# RFID.net
KiCad netlist of a schematic drawn in EAGLE
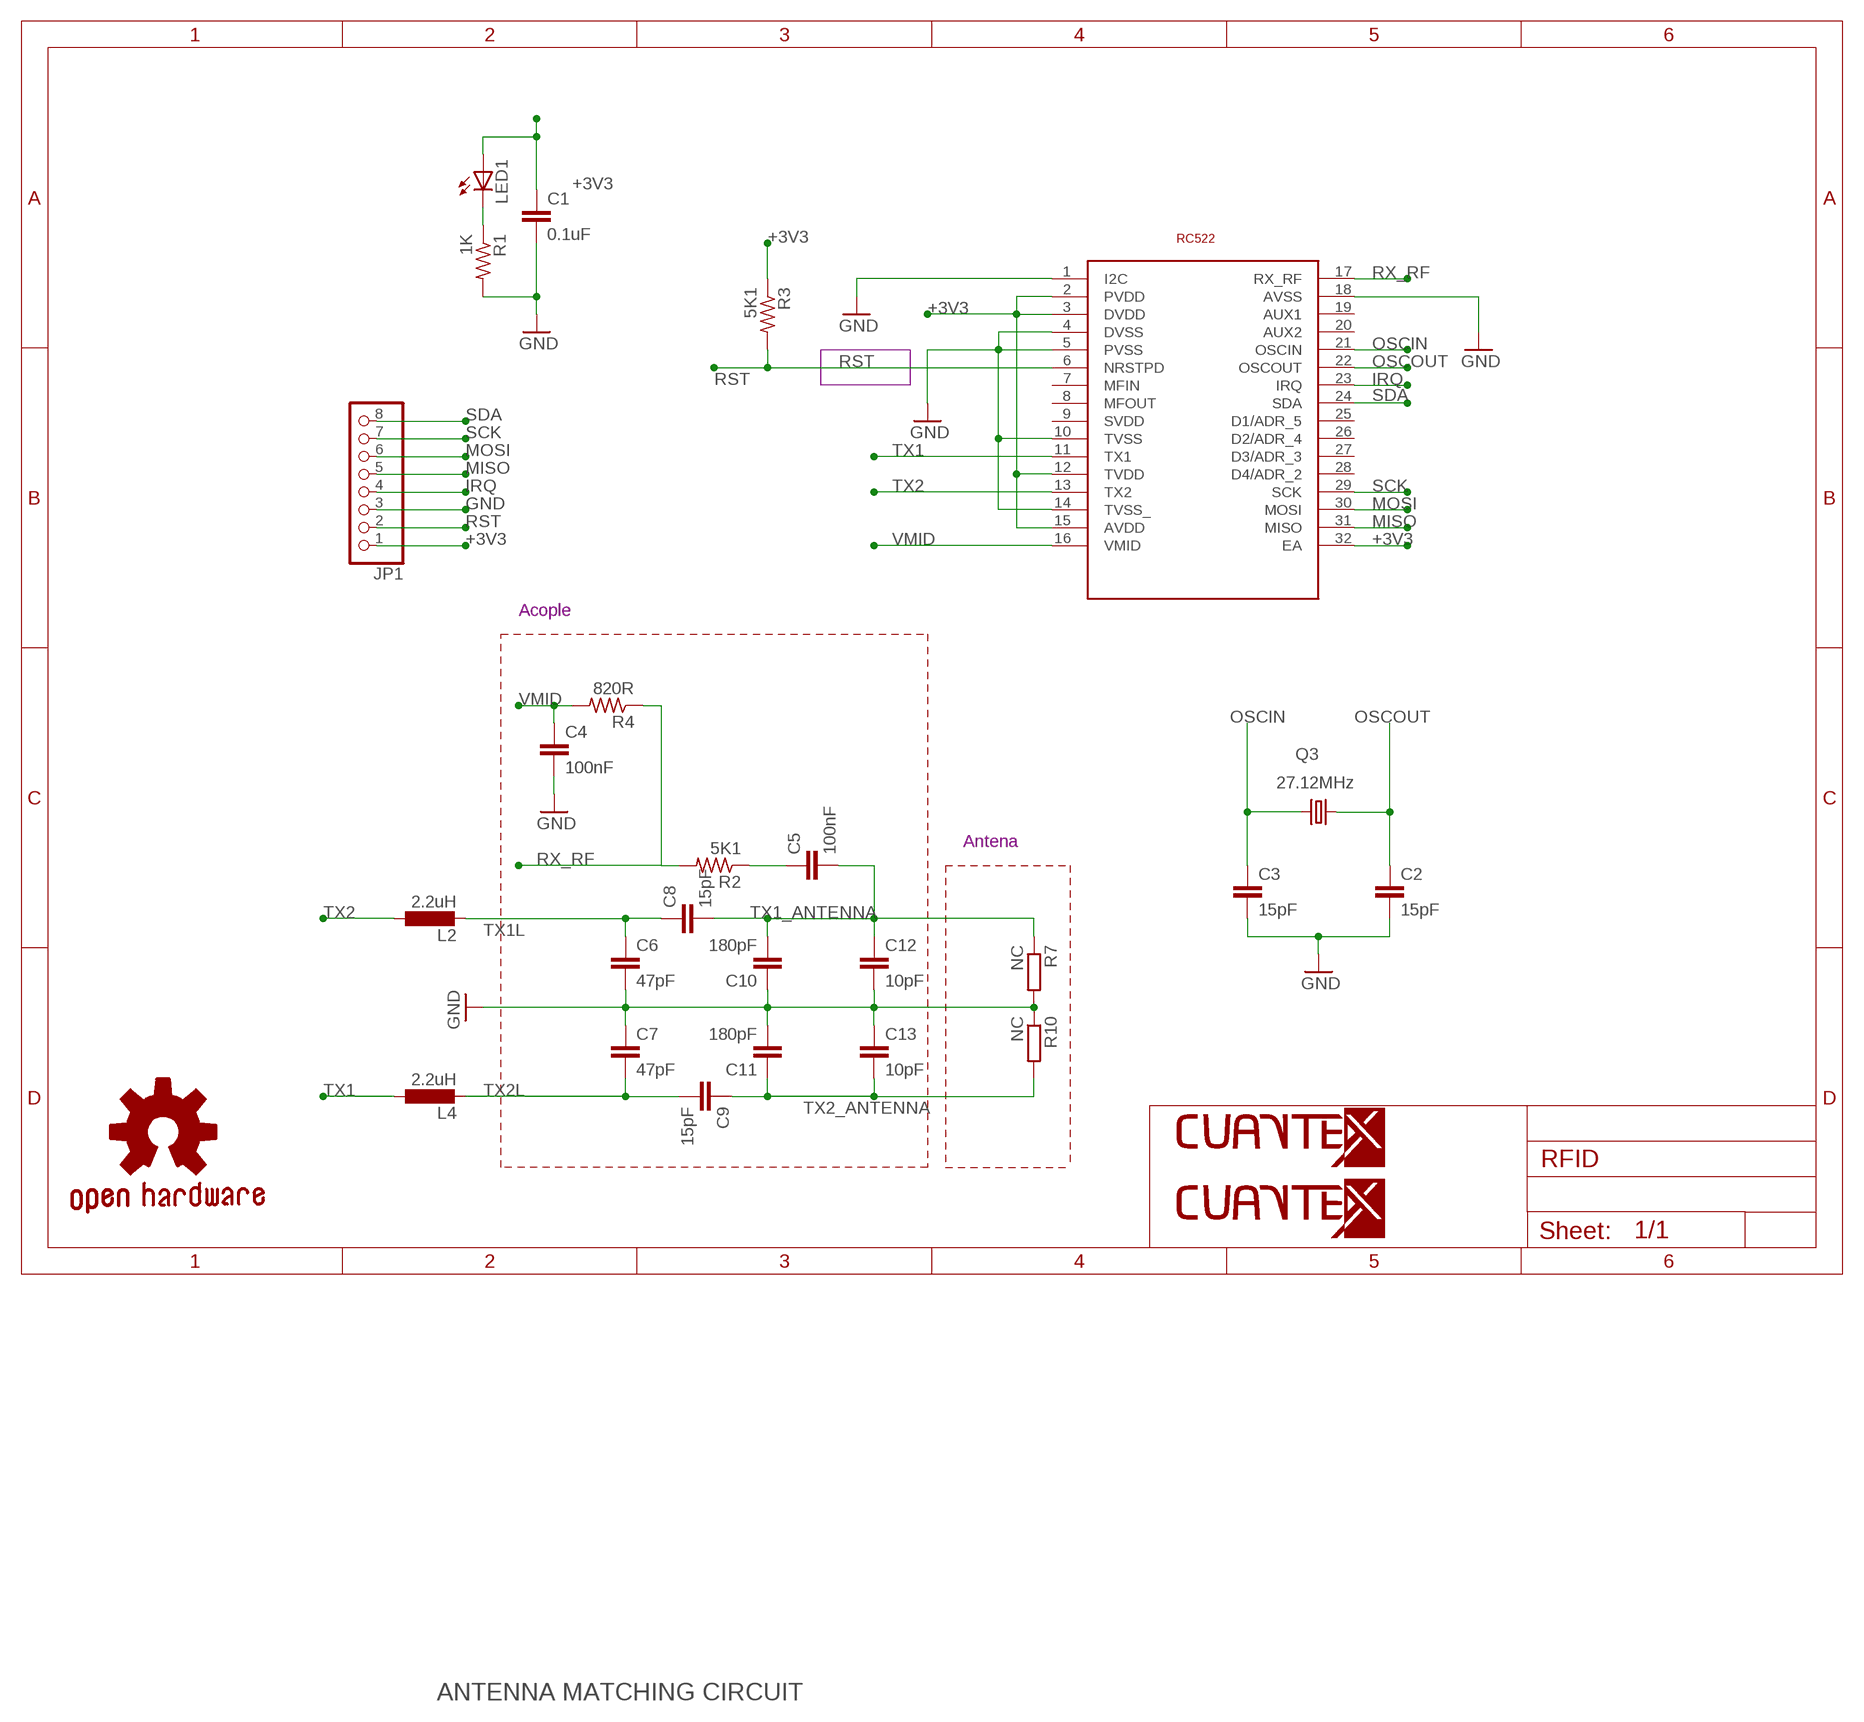
[diagram p0: schematic, sheet 1]

(export (version "E")
  (design (tool "Eeschema 10.0.6"))
  (components
    (comp (ref "C1")
      (value "0.1uF")
      (footprint "eagle-import:C0603K")
      (libsource (lib "eagle-import") (part "resistor_C-EUC0603K"))
    )
    (comp (ref "C2")
      (value "15pF")
      (footprint "eagle-import:C0603K")
      (libsource (lib "eagle-import") (part "C-EUC0603K"))
    )
    (comp (ref "C3")
      (value "15pF")
      (footprint "eagle-import:C0603K")
      (libsource (lib "eagle-import") (part "C-EUC0603K"))
    )
    (comp (ref "C4")
      (value "100nF")
      (footprint "eagle-import:C0603K")
      (libsource (lib "eagle-import") (part "C-EUC0603K"))
    )
    (comp (ref "C5")
      (value "100nF")
      (footprint "eagle-import:C0603K")
      (libsource (lib "eagle-import") (part "C-EUC0603K"))
    )
    (comp (ref "C6")
      (value "47pF")
      (footprint "eagle-import:C0603K")
      (libsource (lib "eagle-import") (part "C-EUC0603K"))
    )
    (comp (ref "C7")
      (value "47pF")
      (footprint "eagle-import:C0603K")
      (libsource (lib "eagle-import") (part "C-EUC0603K"))
    )
    (comp (ref "C8")
      (value "15pF")
      (footprint "eagle-import:C0603K")
      (libsource (lib "eagle-import") (part "C-EUC0603K"))
    )
    (comp (ref "C9")
      (value "15pF")
      (footprint "eagle-import:C0603K")
      (libsource (lib "eagle-import") (part "C-EUC0603K"))
    )
    (comp (ref "C10")
      (value "180pF")
      (footprint "eagle-import:C0603K")
      (libsource (lib "eagle-import") (part "C-EUC0603K"))
    )
    (comp (ref "C11")
      (value "180pF")
      (footprint "eagle-import:C0603K")
      (libsource (lib "eagle-import") (part "C-EUC0603K"))
    )
    (comp (ref "C12")
      (value "10pF")
      (footprint "eagle-import:C0603K")
      (libsource (lib "eagle-import") (part "C-EUC0603K"))
    )
    (comp (ref "C13")
      (value "10pF")
      (footprint "eagle-import:C0603K")
      (libsource (lib "eagle-import") (part "C-EUC0603K"))
    )
    (comp (ref "GOLD_ORB_SM1")
      (value "OSHWLOGO_GOLD_ORB_SM")
      (footprint "eagle-import:OSHW2")
      (libsource (lib "eagle-import") (part "OSHWLOGO_GOLD_ORB_SM"))
    )
    (comp (ref "JP1")
      (value "PINHD-1X8")
      (footprint "eagle-import:1X08")
      (libsource (lib "eagle-import") (part "PINHD-1X8"))
    )
    (comp (ref "L2")
      (value "2.2uH")
      (footprint "eagle-import:L2012C")
      (libsource (lib "eagle-import") (part "L-EUL2012C"))
    )
    (comp (ref "L4")
      (value "2.2uH")
      (footprint "eagle-import:L2012C")
      (libsource (lib "eagle-import") (part "L-EUL2012C"))
    )
    (comp (ref "LED1")
      (value "LED_E")
      (footprint "eagle-import:LED_1206")
      (libsource (lib "eagle-import") (part "LED_E"))
    )
    (comp (ref "Q3")
      (value "27.12MHz")
      (footprint "eagle-import:HC49UP")
      (libsource (lib "eagle-import") (part "CRYSTALHC49UP"))
    )
    (comp (ref "R1")
      (value "1K")
      (footprint "eagle-import:R0603")
      (libsource (lib "eagle-import") (part "R-US_R0603"))
    )
    (comp (ref "R2")
      (value "5K1")
      (footprint "eagle-import:R0603")
      (libsource (lib "eagle-import") (part "R-US_R0603"))
    )
    (comp (ref "R3")
      (value "5K1")
      (footprint "eagle-import:R0603")
      (libsource (lib "eagle-import") (part "R-US_R0603"))
    )
    (comp (ref "R4")
      (value "820R")
      (footprint "eagle-import:R0603")
      (libsource (lib "eagle-import") (part "R-US_R0603"))
    )
    (comp (ref "R7")
      (value "NC")
      (footprint "eagle-import:R0201")
      (libsource (lib "eagle-import") (part "R-EU_R0201"))
    )
    (comp (ref "R10")
      (value "NC")
      (footprint "eagle-import:R0201")
      (libsource (lib "eagle-import") (part "R-EU_R0201"))
    )
    (comp (ref "U$1")
      (value "LOGO-BOT-50MM")
      (footprint "eagle-import:B-50")
      (libsource (lib "eagle-import") (part "LOGO-BOT-50MM"))
    )
    (comp (ref "U$2")
      (value "LOGO-TOP-20MM")
      (footprint "eagle-import:C-0")
      (libsource (lib "eagle-import") (part "LOGO-TOP-20MM"))
    )
    (comp (ref "U1")
      (value "RC522")
      (footprint "eagle-import:HVQFN32")
      (libsource (lib "eagle-import") (part "RC522"))
    )
  )
  (nets
    (net (code "1") (name "/+3V3") (class "Default")
      (node (ref "C1") (pin "1") (pinfunction "1_1") (pintype "passive"))
      (node (ref "JP1") (pin "1") (pinfunction "1_1") (pintype "passive"))
      (node (ref "LED1") (pin "A") (pinfunction "A_A") (pintype "passive"))
      (node (ref "R3") (pin "1") (pinfunction "1_1") (pintype "passive"))
      (node (ref "U1") (pin "12") (pinfunction "TVDD_12") (pintype "bidirectional"))
      (node (ref "U1") (pin "15") (pinfunction "AVDD_15") (pintype "bidirectional"))
      (node (ref "U1") (pin "2") (pinfunction "PVDD_2") (pintype "bidirectional"))
      (node (ref "U1") (pin "3") (pinfunction "DVDD_3") (pintype "bidirectional"))
      (node (ref "U1") (pin "32") (pinfunction "EA_32") (pintype "bidirectional"))
    )
    (net (code "2") (name "/IRQ") (class "Default")
      (node (ref "JP1") (pin "4") (pinfunction "4_4") (pintype "passive"))
      (node (ref "U1") (pin "23") (pinfunction "IRQ_23") (pintype "bidirectional"))
    )
    (net (code "3") (name "/MISO") (class "Default")
      (node (ref "JP1") (pin "5") (pinfunction "5_5") (pintype "passive"))
      (node (ref "U1") (pin "31") (pinfunction "MISO_31") (pintype "bidirectional"))
    )
    (net (code "4") (name "/MOSI") (class "Default")
      (node (ref "JP1") (pin "6") (pinfunction "6_6") (pintype "passive"))
      (node (ref "U1") (pin "30") (pinfunction "MOSI_30") (pintype "bidirectional"))
    )
    (net (code "5") (name "/OSCIN") (class "Default")
      (node (ref "C3") (pin "1") (pinfunction "1_1") (pintype "passive"))
      (node (ref "Q3") (pin "2") (pinfunction "2_2") (pintype "passive"))
      (node (ref "U1") (pin "21") (pinfunction "OSCIN_21") (pintype "bidirectional"))
    )
    (net (code "6") (name "/OSCOUT") (class "Default")
      (node (ref "C2") (pin "1") (pinfunction "1_1") (pintype "passive"))
      (node (ref "Q3") (pin "1") (pinfunction "1_1") (pintype "passive"))
      (node (ref "U1") (pin "22") (pinfunction "OSCOUT_22") (pintype "bidirectional"))
    )
    (net (code "7") (name "/RST") (class "Default")
      (node (ref "JP1") (pin "2") (pinfunction "2_2") (pintype "passive"))
      (node (ref "R3") (pin "2") (pinfunction "2_2") (pintype "passive"))
      (node (ref "U1") (pin "6") (pinfunction "NRSTPD_6") (pintype "bidirectional"))
    )
    (net (code "8") (name "/RX_RF") (class "Default")
      (node (ref "R2") (pin "2") (pinfunction "2_2") (pintype "passive"))
      (node (ref "R4") (pin "1") (pinfunction "1_1") (pintype "passive"))
      (node (ref "U1") (pin "17") (pinfunction "RX_RF_17") (pintype "bidirectional"))
    )
    (net (code "9") (name "/SCK") (class "Default")
      (node (ref "JP1") (pin "7") (pinfunction "7_7") (pintype "passive"))
      (node (ref "U1") (pin "29") (pinfunction "SCK_29") (pintype "bidirectional"))
    )
    (net (code "10") (name "/SDA") (class "Default")
      (node (ref "JP1") (pin "8") (pinfunction "8_8") (pintype "passive"))
      (node (ref "U1") (pin "24") (pinfunction "SDA_24") (pintype "bidirectional"))
    )
    (net (code "11") (name "/TX1") (class "Default")
      (node (ref "L4") (pin "1") (pinfunction "1_1") (pintype "passive"))
      (node (ref "U1") (pin "11") (pinfunction "TX1_11") (pintype "bidirectional"))
    )
    (net (code "12") (name "/TX1L") (class "Default")
      (node (ref "C6") (pin "1") (pinfunction "1_1") (pintype "passive"))
      (node (ref "C8") (pin "1") (pinfunction "1_1") (pintype "passive"))
      (node (ref "L2") (pin "2") (pinfunction "2_2") (pintype "passive"))
    )
    (net (code "13") (name "/TX1_ANTENNA") (class "Default")
      (node (ref "C10") (pin "2") (pinfunction "2_2") (pintype "passive"))
      (node (ref "C12") (pin "1") (pinfunction "1_1") (pintype "passive"))
      (node (ref "C5") (pin "2") (pinfunction "2_2") (pintype "passive"))
      (node (ref "C8") (pin "2") (pinfunction "2_2") (pintype "passive"))
      (node (ref "R7") (pin "1") (pinfunction "1_1") (pintype "passive"))
    )
    (net (code "14") (name "/TX2") (class "Default")
      (node (ref "L2") (pin "1") (pinfunction "1_1") (pintype "passive"))
      (node (ref "U1") (pin "13") (pinfunction "TX2_13") (pintype "bidirectional"))
    )
    (net (code "15") (name "/TX2L") (class "Default")
      (node (ref "C7") (pin "2") (pinfunction "2_2") (pintype "passive"))
      (node (ref "C9") (pin "2") (pinfunction "2_2") (pintype "passive"))
      (node (ref "L4") (pin "2") (pinfunction "2_2") (pintype "passive"))
    )
    (net (code "16") (name "/TX2_ANTENNA") (class "Default")
      (node (ref "C11") (pin "1") (pinfunction "1_1") (pintype "passive"))
      (node (ref "C13") (pin "2") (pinfunction "2_2") (pintype "passive"))
      (node (ref "C9") (pin "1") (pinfunction "1_1") (pintype "passive"))
      (node (ref "R10") (pin "2") (pinfunction "2_2") (pintype "passive"))
    )
    (net (code "17") (name "/VMID") (class "Default")
      (node (ref "C4") (pin "1") (pinfunction "1_1") (pintype "passive"))
      (node (ref "R4") (pin "2") (pinfunction "2_2") (pintype "passive"))
      (node (ref "U1") (pin "16") (pinfunction "VMID_16") (pintype "bidirectional"))
    )
    (net (code "18") (name "GND") (class "Default")
      (node (ref "C1") (pin "2") (pinfunction "2_2") (pintype "passive"))
      (node (ref "C10") (pin "1") (pinfunction "1_1") (pintype "passive"))
      (node (ref "C11") (pin "2") (pinfunction "2_2") (pintype "passive"))
      (node (ref "C12") (pin "2") (pinfunction "2_2") (pintype "passive"))
      (node (ref "C13") (pin "1") (pinfunction "1_1") (pintype "passive"))
      (node (ref "C2") (pin "2") (pinfunction "2_2") (pintype "passive"))
      (node (ref "C3") (pin "2") (pinfunction "2_2") (pintype "passive"))
      (node (ref "C4") (pin "2") (pinfunction "2_2") (pintype "passive"))
      (node (ref "C6") (pin "2") (pinfunction "2_2") (pintype "passive"))
      (node (ref "C7") (pin "1") (pinfunction "1_1") (pintype "passive"))
      (node (ref "JP1") (pin "3") (pinfunction "3_3") (pintype "passive"))
      (node (ref "R1") (pin "2") (pinfunction "2_2") (pintype "passive"))
      (node (ref "R10") (pin "1") (pinfunction "1_1") (pintype "passive"))
      (node (ref "R7") (pin "2") (pinfunction "2_2") (pintype "passive"))
      (node (ref "U1") (pin "1") (pinfunction "I2C_1") (pintype "bidirectional"))
      (node (ref "U1") (pin "10") (pinfunction "TVSS_10") (pintype "bidirectional"))
      (node (ref "U1") (pin "14") (pinfunction "TVSS__14") (pintype "bidirectional"))
      (node (ref "U1") (pin "18") (pinfunction "AVSS_18") (pintype "bidirectional"))
      (node (ref "U1") (pin "4") (pinfunction "DVSS_4") (pintype "bidirectional"))
      (node (ref "U1") (pin "5") (pinfunction "PVSS_5") (pintype "bidirectional"))
    )
    (net (code "19") (name "Net-(C5-Pad1)") (class "Default")
      (node (ref "C5") (pin "1") (pinfunction "1_1") (pintype "passive"))
      (node (ref "R2") (pin "1") (pinfunction "1_1") (pintype "passive"))
    )
    (net (code "20") (name "Net-(LED1-PadC)") (class "Default")
      (node (ref "LED1") (pin "C") (pinfunction "C_C") (pintype "passive"))
      (node (ref "R1") (pin "1") (pinfunction "1_1") (pintype "passive"))
    )
    (net (code "21") (name "unconnected-(U1-AUX1-Pad19)") (class "Default")
      (node (ref "U1") (pin "19") (pinfunction "AUX1_19") (pintype "bidirectional"))
    )
    (net (code "22") (name "unconnected-(U1-AUX2-Pad20)") (class "Default")
      (node (ref "U1") (pin "20") (pinfunction "AUX2_20") (pintype "bidirectional"))
    )
    (net (code "23") (name "unconnected-(U1-D1{slash}ADR_5-Pad25)") (class "Default")
      (node (ref "U1") (pin "25") (pinfunction "D1/ADR_5_25") (pintype "bidirectional"))
    )
    (net (code "24") (name "unconnected-(U1-D2{slash}ADR_4-Pad26)") (class "Default")
      (node (ref "U1") (pin "26") (pinfunction "D2/ADR_4_26") (pintype "bidirectional"))
    )
    (net (code "25") (name "unconnected-(U1-D3{slash}ADR_3-Pad27)") (class "Default")
      (node (ref "U1") (pin "27") (pinfunction "D3/ADR_3_27") (pintype "bidirectional"))
    )
    (net (code "26") (name "unconnected-(U1-D4{slash}ADR_2-Pad28)") (class "Default")
      (node (ref "U1") (pin "28") (pinfunction "D4/ADR_2_28") (pintype "bidirectional"))
    )
    (net (code "27") (name "unconnected-(U1-MFIN-Pad7)") (class "Default")
      (node (ref "U1") (pin "7") (pinfunction "MFIN_7") (pintype "bidirectional"))
    )
    (net (code "28") (name "unconnected-(U1-MFOUT-Pad8)") (class "Default")
      (node (ref "U1") (pin "8") (pinfunction "MFOUT_8") (pintype "bidirectional"))
    )
    (net (code "29") (name "unconnected-(U1-SVDD-Pad9)") (class "Default")
      (node (ref "U1") (pin "9") (pinfunction "SVDD_9") (pintype "bidirectional"))
    )
  )
)
